# PowerRhythm32.net
KiCad netlist of a schematic drawn in EAGLE
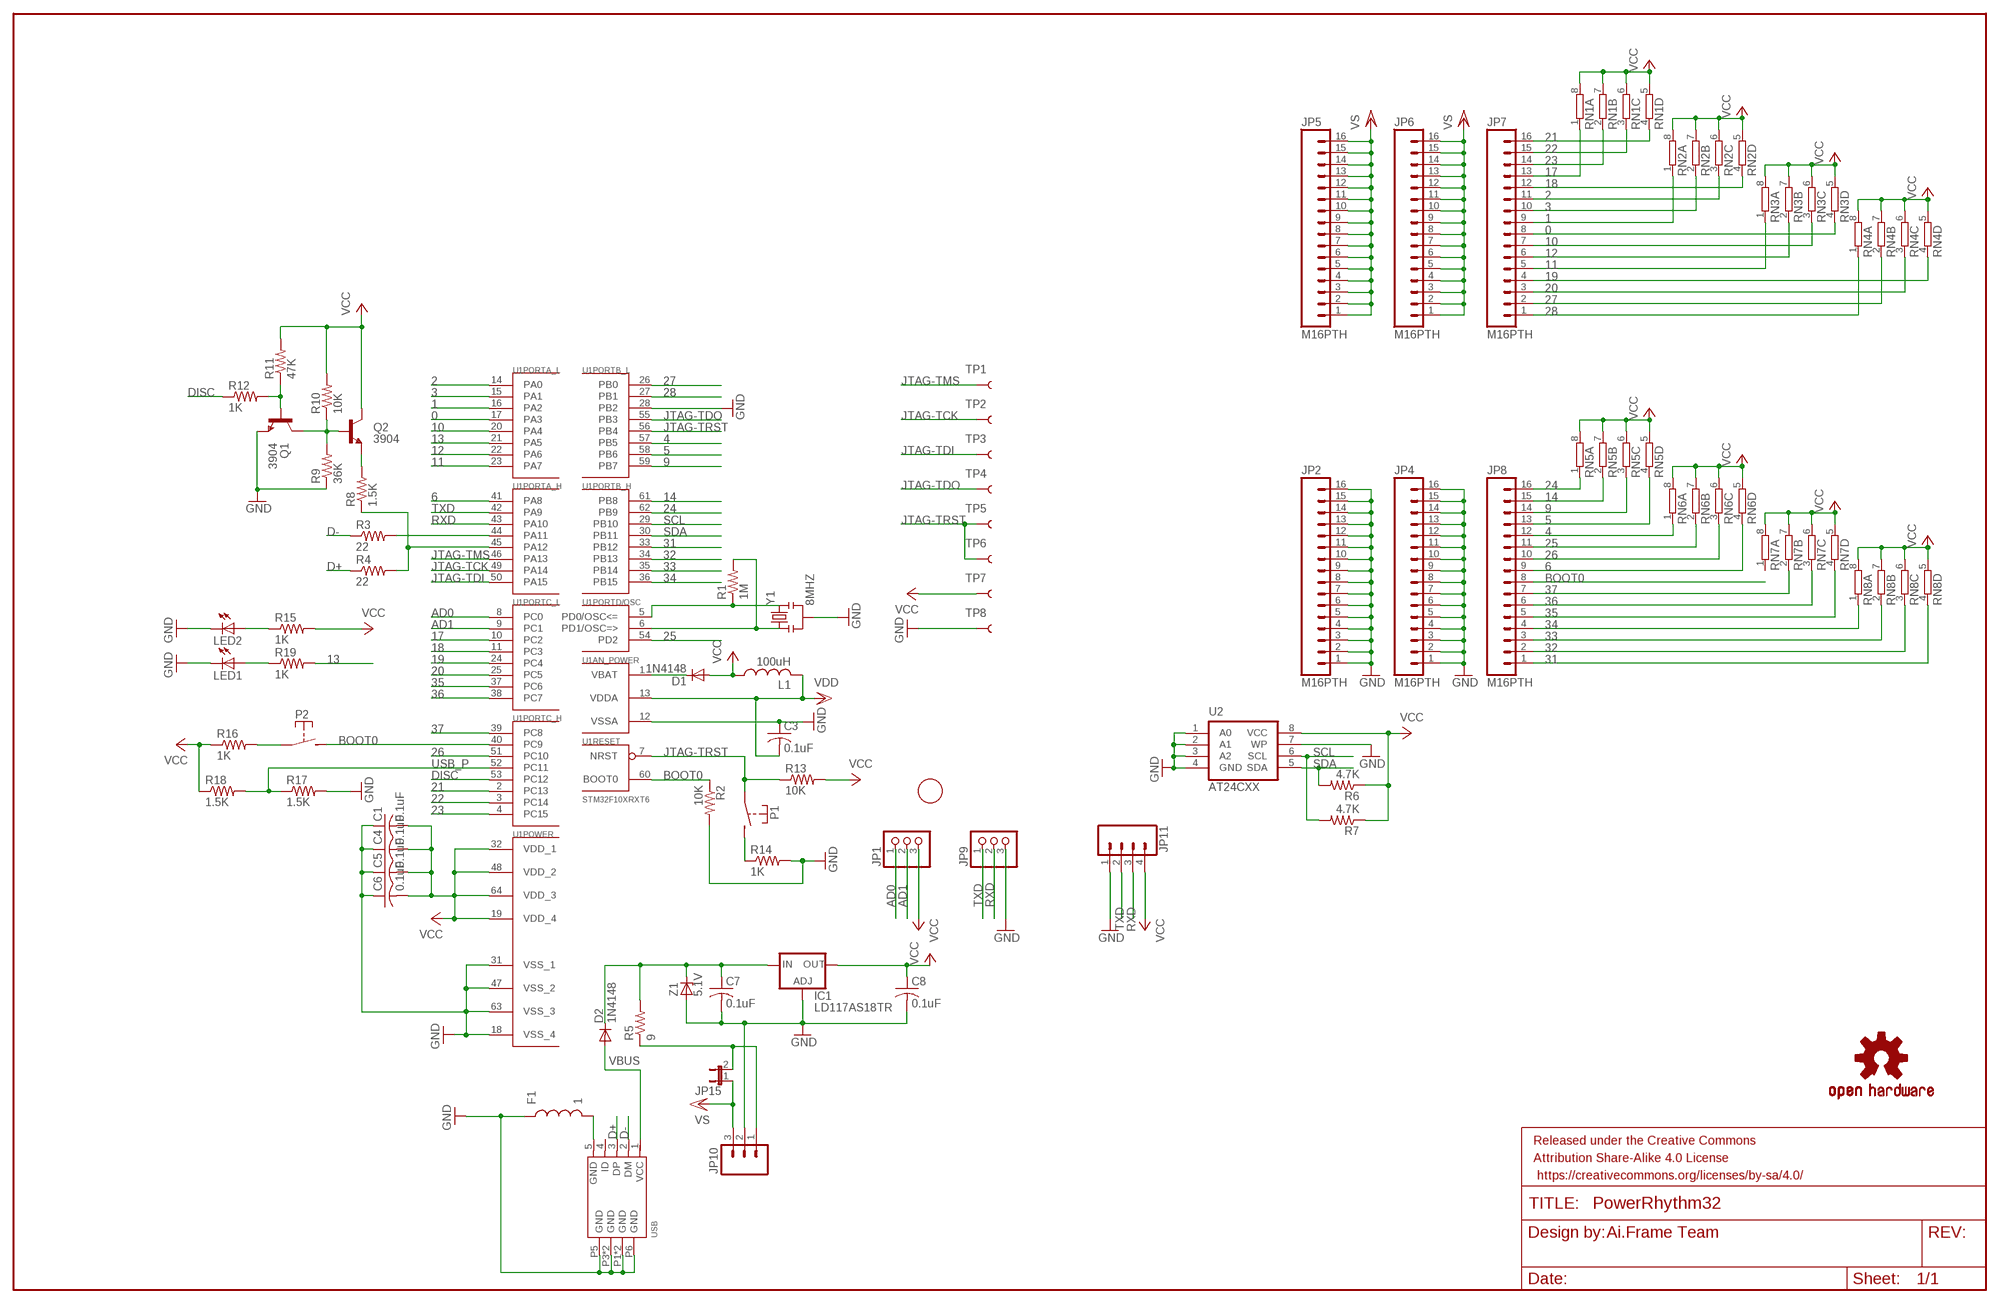
[diagram p0: schematic, sheet 1]

(export (version "E")
  (design (tool "Eeschema 10.0.6"))
  (components
    (comp (ref "C1")
      (value "0.1uF")
      (footprint "eagle-import:C0603K")
      (libsource (lib "eagle-import") (part "C-USC0603K"))
    )
    (comp (ref "C3")
      (value "0.1uF")
      (footprint "eagle-import:C0603K")
      (libsource (lib "eagle-import") (part "C-USC0603K"))
    )
    (comp (ref "C4")
      (value "0.1uF")
      (footprint "eagle-import:C0603K")
      (libsource (lib "eagle-import") (part "C-USC0603K"))
    )
    (comp (ref "C5")
      (value "0.1uF")
      (footprint "eagle-import:C0603K")
      (libsource (lib "eagle-import") (part "C-USC0603K"))
    )
    (comp (ref "C6")
      (value "0.1uF")
      (footprint "eagle-import:C0603K")
      (libsource (lib "eagle-import") (part "C-USC0603K"))
    )
    (comp (ref "C7")
      (value "0.1uF")
      (footprint "eagle-import:C0603K")
      (libsource (lib "eagle-import") (part "C-USC0603K"))
    )
    (comp (ref "C8")
      (value "0.1uF")
      (footprint "eagle-import:C0603K")
      (libsource (lib "eagle-import") (part "C-USC0603K"))
    )
    (comp (ref "D1")
      (value "1N4148")
      (footprint "eagle-import:SOD123")
      (libsource (lib "eagle-import") (part "DIODE-SOD123"))
    )
    (comp (ref "D2")
      (value "1N4148")
      (footprint "eagle-import:SOD123")
      (libsource (lib "eagle-import") (part "DIODE-SOD123"))
    )
    (comp (ref "F1")
      (value "1")
      (footprint "eagle-import:0805")
      (libsource (lib "eagle-import") (part "INDUCTOR0805"))
    )
    (comp (ref "FRAME1")
      (value "FRAME-LEDGER")
      (footprint "eagle-import:CREATIVE_COMMONS")
      (libsource (lib "eagle-import") (part "FRAME-LEDGER"))
    )
    (comp (ref "IC1")
      (value "LD117AS18TR")
      (footprint "eagle-import:SOT223")
      (libsource (lib "eagle-import") (part "LD117A?S18TR"))
    )
    (comp (ref "JP1")
      (value "PINHD-1X3")
      (footprint "eagle-import:1X03")
      (libsource (lib "eagle-import") (part "PINHD-1X3"))
    )
    (comp (ref "JP2")
      (value "M16PTH")
      (footprint "eagle-import:1X16")
      (libsource (lib "eagle-import") (part "M16PTH"))
    )
    (comp (ref "JP4")
      (value "M16PTH")
      (footprint "eagle-import:1X16")
      (libsource (lib "eagle-import") (part "M16PTH"))
    )
    (comp (ref "JP5")
      (value "M16PTH")
      (footprint "eagle-import:1X16")
      (libsource (lib "eagle-import") (part "M16PTH"))
    )
    (comp (ref "JP6")
      (value "M16PTH")
      (footprint "eagle-import:1X16")
      (libsource (lib "eagle-import") (part "M16PTH"))
    )
    (comp (ref "JP7")
      (value "M16PTH")
      (footprint "eagle-import:1X16")
      (libsource (lib "eagle-import") (part "M16PTH"))
    )
    (comp (ref "JP8")
      (value "M16PTH")
      (footprint "eagle-import:1X16")
      (libsource (lib "eagle-import") (part "M16PTH"))
    )
    (comp (ref "JP9")
      (value "PINHD-1X3")
      (footprint "eagle-import:1X03")
      (libsource (lib "eagle-import") (part "PINHD-1X3"))
    )
    (comp (ref "JP10")
      (value "M03SCREW_LOCK")
      (footprint "eagle-import:SCREWTERMINAL-3.5MM-3_LOCK.007S")
      (libsource (lib "eagle-import") (part "M03SCREW_LOCK"))
    )
    (comp (ref "JP11")
      (value "M04PTH")
      (footprint "eagle-import:1X04")
      (libsource (lib "eagle-import") (part "M04PTH"))
    )
    (comp (ref "JP15")
      (value "JUMPER-2PTH")
      (footprint "eagle-import:1X02")
      (libsource (lib "eagle-import") (part "JUMPER-2PTH"))
    )
    (comp (ref "L1")
      (value "100uH")
      (footprint "eagle-import:L2012C")
      (libsource (lib "eagle-import") (part "L-USL2012C"))
    )
    (comp (ref "LED1")
      (value "LEDCHIP-LED0603")
      (footprint "eagle-import:CHIP-LED0603")
      (libsource (lib "eagle-import") (part "LEDCHIP-LED0603"))
    )
    (comp (ref "LED2")
      (value "LEDCHIP-LED0603")
      (footprint "eagle-import:CHIP-LED0603")
      (libsource (lib "eagle-import") (part "LEDCHIP-LED0603"))
    )
    (comp (ref "LOGO1")
      (value "OSHW-LOGOS")
      (footprint "eagle-import:OSHW-LOGO-S")
      (libsource (lib "eagle-import") (part "OSHW-LOGOS"))
    )
    (comp (ref "P1")
      (value "TMAV433BAA")
      (footprint "eagle-import:TMAV433BAA")
      (libsource (lib "eagle-import") (part "TMAV433BAA"))
    )
    (comp (ref "P2")
      (value "TMAV433BAA")
      (footprint "eagle-import:TMAV433BAA")
      (libsource (lib "eagle-import") (part "TMAV433BAA"))
    )
    (comp (ref "Q1")
      (value "3904")
      (footprint "eagle-import:SOT23-3")
      (libsource (lib "eagle-import") (part "TRANSISTOR_NPNMMBT2222A"))
    )
    (comp (ref "Q2")
      (value "3904")
      (footprint "eagle-import:SOT23-3")
      (libsource (lib "eagle-import") (part "TRANSISTOR_NPNMMBT2222A"))
    )
    (comp (ref "R1")
      (value "1M")
      (footprint "eagle-import:R0603")
      (libsource (lib "eagle-import") (part "R-US_R0603"))
    )
    (comp (ref "R2")
      (value "10K")
      (footprint "eagle-import:R0603")
      (libsource (lib "eagle-import") (part "R-US_R0603"))
    )
    (comp (ref "R3")
      (value "22")
      (footprint "eagle-import:R0603")
      (libsource (lib "eagle-import") (part "R-US_R0603"))
    )
    (comp (ref "R4")
      (value "22")
      (footprint "eagle-import:R0603")
      (libsource (lib "eagle-import") (part "R-US_R0603"))
    )
    (comp (ref "R5")
      (value "9")
      (footprint "eagle-import:R1206")
      (libsource (lib "eagle-import") (part "R-US_R1206"))
    )
    (comp (ref "R6")
      (value "4.7K")
      (footprint "eagle-import:R0603")
      (libsource (lib "eagle-import") (part "R-US_R0603"))
    )
    (comp (ref "R7")
      (value "4.7K")
      (footprint "eagle-import:R0603")
      (libsource (lib "eagle-import") (part "R-US_R0603"))
    )
    (comp (ref "R8")
      (value "1.5K")
      (footprint "eagle-import:R0603")
      (libsource (lib "eagle-import") (part "R-US_R0603"))
    )
    (comp (ref "R9")
      (value "36K")
      (footprint "eagle-import:R0603")
      (libsource (lib "eagle-import") (part "R-US_R0603"))
    )
    (comp (ref "R10")
      (value "10K")
      (footprint "eagle-import:R0603")
      (libsource (lib "eagle-import") (part "R-US_R0603"))
    )
    (comp (ref "R11")
      (value "47K")
      (footprint "eagle-import:R0603")
      (libsource (lib "eagle-import") (part "R-US_R0603"))
    )
    (comp (ref "R12")
      (value "1K")
      (footprint "eagle-import:R0603")
      (libsource (lib "eagle-import") (part "R-US_R0603"))
    )
    (comp (ref "R13")
      (value "10K")
      (footprint "eagle-import:R0603")
      (libsource (lib "eagle-import") (part "R-US_R0603"))
    )
    (comp (ref "R14")
      (value "1K")
      (footprint "eagle-import:R0603")
      (libsource (lib "eagle-import") (part "R-US_R0603"))
    )
    (comp (ref "R15")
      (value "1K")
      (footprint "eagle-import:R0603")
      (libsource (lib "eagle-import") (part "R-US_R0603"))
    )
    (comp (ref "R16")
      (value "1K")
      (footprint "eagle-import:R0603")
      (libsource (lib "eagle-import") (part "R-US_R0603"))
    )
    (comp (ref "R17")
      (value "1.5K")
      (footprint "eagle-import:R0603")
      (libsource (lib "eagle-import") (part "R-US_R0603"))
    )
    (comp (ref "R18")
      (value "1.5K")
      (footprint "eagle-import:R0603")
      (libsource (lib "eagle-import") (part "R-US_R0603"))
    )
    (comp (ref "R19")
      (value "1K")
      (footprint "eagle-import:R0603")
      (libsource (lib "eagle-import") (part "R-US_R0603"))
    )
    (comp (ref "RN1")
      (value "4R-N0603-ARC")
      (footprint "eagle-import:0603-ARC")
      (libsource (lib "eagle-import") (part "4R-N0603-ARC"))
    )
    (comp (ref "RN2")
      (value "4R-N0603-ARC")
      (footprint "eagle-import:0603-ARC")
      (libsource (lib "eagle-import") (part "4R-N0603-ARC"))
    )
    (comp (ref "RN3")
      (value "4R-N0603-ARC")
      (footprint "eagle-import:0603-ARC")
      (libsource (lib "eagle-import") (part "4R-N0603-ARC"))
    )
    (comp (ref "RN4")
      (value "4R-N0603-ARC")
      (footprint "eagle-import:0603-ARC")
      (libsource (lib "eagle-import") (part "4R-N0603-ARC"))
    )
    (comp (ref "RN5")
      (value "4R-N0603-ARC")
      (footprint "eagle-import:0603-ARC")
      (libsource (lib "eagle-import") (part "4R-N0603-ARC"))
    )
    (comp (ref "RN6")
      (value "4R-N0603-ARC")
      (footprint "eagle-import:0603-ARC")
      (libsource (lib "eagle-import") (part "4R-N0603-ARC"))
    )
    (comp (ref "RN7")
      (value "4R-N0603-ARC")
      (footprint "eagle-import:0603-ARC")
      (libsource (lib "eagle-import") (part "4R-N0603-ARC"))
    )
    (comp (ref "RN8")
      (value "4R-N0603-ARC")
      (footprint "eagle-import:0603-ARC")
      (libsource (lib "eagle-import") (part "4R-N0603-ARC"))
    )
    (comp (ref "TP1")
      (value "TEST-POINT3X5")
      (footprint "eagle-import:PAD.03X.05")
      (libsource (lib "eagle-import") (part "TEST-POINT3X5"))
    )
    (comp (ref "TP2")
      (value "TEST-POINT3X5")
      (footprint "eagle-import:PAD.03X.05")
      (libsource (lib "eagle-import") (part "TEST-POINT3X5"))
    )
    (comp (ref "TP3")
      (value "TEST-POINT3X5")
      (footprint "eagle-import:PAD.03X.05")
      (libsource (lib "eagle-import") (part "TEST-POINT3X5"))
    )
    (comp (ref "TP4")
      (value "TEST-POINT3X5")
      (footprint "eagle-import:PAD.03X.05")
      (libsource (lib "eagle-import") (part "TEST-POINT3X5"))
    )
    (comp (ref "TP5")
      (value "TEST-POINT3X5")
      (footprint "eagle-import:PAD.03X.05")
      (libsource (lib "eagle-import") (part "TEST-POINT3X5"))
    )
    (comp (ref "TP6")
      (value "TEST-POINT3X5")
      (footprint "eagle-import:PAD.03X.05")
      (libsource (lib "eagle-import") (part "TEST-POINT3X5"))
    )
    (comp (ref "TP7")
      (value "TEST-POINT3X5")
      (footprint "eagle-import:PAD.03X.05")
      (libsource (lib "eagle-import") (part "TEST-POINT3X5"))
    )
    (comp (ref "TP8")
      (value "TEST-POINT3X5")
      (footprint "eagle-import:PAD.03X.05")
      (libsource (lib "eagle-import") (part "TEST-POINT3X5"))
    )
    (comp (ref "U$1")
      (value "FIDUCIAL")
      (footprint "eagle-import:FIDUCIAL_1MM")
      (libsource (lib "eagle-import") (part "FIDUCIAL"))
    )
    (comp (ref "U1")
      (value "STM32F10XRXT6")
      (footprint "eagle-import:TQFP64")
      (libsource (lib "eagle-import") (part "STM32F10XRXT6"))
    )
    (comp (ref "U2")
      (value "AT24CXX")
      (footprint "eagle-import:SO08-8S1")
      (libsource (lib "eagle-import") (part "AT24CXX"))
    )
    (comp (ref "USB")
      (value "MICRO-USB5+4P'5+6P'")
      (footprint "eagle-import:MICRO-USB5+6P-SMD-0.65-AB")
      (libsource (lib "eagle-import") (part "MICRO-USB5+4P'5+6P'"))
    )
    (comp (ref "Y1")
      (value "8MHZ")
      (footprint "eagle-import:RESONATOR-SMD")
      (libsource (lib "eagle-import") (part "RESONATOR8MHZ"))
    )
    (comp (ref "Z1")
      (value "5.1V")
      (footprint "eagle-import:SOD80C")
      (libsource (lib "eagle-import") (part "ZENER-DIODESOD80C"))
    )
  )
  (nets
    (net (code "1") (name "/0") (class "Default")
      (node (ref "JP7") (pin "8") (pinfunction "8_8") (pintype "passive"))
      (node (ref "RN3") (pin "4") (pinfunction "1_4") (pintype "passive"))
      (node (ref "U1") (pin "17") (pinfunction "PA3_17") (pintype "bidirectional"))
    )
    (net (code "2") (name "/1") (class "Default")
      (node (ref "JP7") (pin "9") (pinfunction "9_9") (pintype "passive"))
      (node (ref "RN2") (pin "1") (pinfunction "1_1") (pintype "passive"))
      (node (ref "U1") (pin "16") (pinfunction "PA2_16") (pintype "bidirectional"))
    )
    (net (code "3") (name "/2") (class "Default")
      (node (ref "JP7") (pin "11") (pinfunction "11_11") (pintype "passive"))
      (node (ref "RN2") (pin "3") (pinfunction "1_3") (pintype "passive"))
      (node (ref "U1") (pin "14") (pinfunction "PA0_14") (pintype "bidirectional"))
    )
    (net (code "4") (name "/3") (class "Default")
      (node (ref "JP7") (pin "10") (pinfunction "10_10") (pintype "passive"))
      (node (ref "RN2") (pin "2") (pinfunction "1_2") (pintype "passive"))
      (node (ref "U1") (pin "15") (pinfunction "PA1_15") (pintype "bidirectional"))
    )
    (net (code "5") (name "/4") (class "Default")
      (node (ref "JP8") (pin "12") (pinfunction "12_12") (pintype "passive"))
      (node (ref "RN6") (pin "1") (pinfunction "1_1") (pintype "passive"))
      (node (ref "U1") (pin "57") (pinfunction "PB5_57") (pintype "bidirectional"))
    )
    (net (code "6") (name "/5") (class "Default")
      (node (ref "JP8") (pin "13") (pinfunction "13_13") (pintype "passive"))
      (node (ref "RN5") (pin "4") (pinfunction "1_4") (pintype "passive"))
      (node (ref "U1") (pin "58") (pinfunction "PB6_58") (pintype "bidirectional"))
    )
    (net (code "7") (name "/6") (class "Default")
      (node (ref "JP8") (pin "9") (pinfunction "9_9") (pintype "passive"))
      (node (ref "RN6") (pin "4") (pinfunction "1_4") (pintype "passive"))
      (node (ref "U1") (pin "41") (pinfunction "PA8_41") (pintype "bidirectional"))
    )
    (net (code "8") (name "/9") (class "Default")
      (node (ref "JP8") (pin "14") (pinfunction "14_14") (pintype "passive"))
      (node (ref "RN5") (pin "3") (pinfunction "1_3") (pintype "passive"))
      (node (ref "U1") (pin "59") (pinfunction "PB7_59") (pintype "bidirectional"))
    )
    (net (code "9") (name "/10") (class "Default")
      (node (ref "JP7") (pin "7") (pinfunction "7_7") (pintype "passive"))
      (node (ref "RN3") (pin "3") (pinfunction "1_3") (pintype "passive"))
      (node (ref "U1") (pin "20") (pinfunction "PA4_20") (pintype "bidirectional"))
    )
    (net (code "10") (name "/11") (class "Default")
      (node (ref "JP7") (pin "5") (pinfunction "5_5") (pintype "passive"))
      (node (ref "RN3") (pin "1") (pinfunction "1_1") (pintype "passive"))
      (node (ref "U1") (pin "23") (pinfunction "PA7_23") (pintype "bidirectional"))
    )
    (net (code "11") (name "/12") (class "Default")
      (node (ref "JP7") (pin "6") (pinfunction "6_6") (pintype "passive"))
      (node (ref "RN3") (pin "2") (pinfunction "1_2") (pintype "passive"))
      (node (ref "U1") (pin "22") (pinfunction "PA6_22") (pintype "bidirectional"))
    )
    (net (code "12") (name "/13") (class "Default")
      (node (ref "R19") (pin "2") (pinfunction "2_2") (pintype "passive"))
      (node (ref "U1") (pin "21") (pinfunction "PA5_21") (pintype "bidirectional"))
    )
    (net (code "13") (name "/14") (class "Default")
      (node (ref "JP8") (pin "15") (pinfunction "15_15") (pintype "passive"))
      (node (ref "RN5") (pin "2") (pinfunction "1_2") (pintype "passive"))
      (node (ref "U1") (pin "61") (pinfunction "PB8_61") (pintype "bidirectional"))
    )
    (net (code "14") (name "/17") (class "Default")
      (node (ref "JP7") (pin "13") (pinfunction "13_13") (pintype "passive"))
      (node (ref "RN1") (pin "1") (pinfunction "1_1") (pintype "passive"))
      (node (ref "U1") (pin "10") (pinfunction "PC2_10") (pintype "bidirectional"))
    )
    (net (code "15") (name "/18") (class "Default")
      (node (ref "JP7") (pin "12") (pinfunction "12_12") (pintype "passive"))
      (node (ref "RN2") (pin "4") (pinfunction "1_4") (pintype "passive"))
      (node (ref "U1") (pin "11") (pinfunction "PC3_11") (pintype "bidirectional"))
    )
    (net (code "16") (name "/19") (class "Default")
      (node (ref "JP7") (pin "4") (pinfunction "4_4") (pintype "passive"))
      (node (ref "RN4") (pin "4") (pinfunction "1_4") (pintype "passive"))
      (node (ref "U1") (pin "24") (pinfunction "PC4_24") (pintype "bidirectional"))
    )
    (net (code "17") (name "/20") (class "Default")
      (node (ref "JP7") (pin "3") (pinfunction "3_3") (pintype "passive"))
      (node (ref "RN4") (pin "3") (pinfunction "1_3") (pintype "passive"))
      (node (ref "U1") (pin "25") (pinfunction "PC5_25") (pintype "bidirectional"))
    )
    (net (code "18") (name "/21") (class "Default")
      (node (ref "JP7") (pin "16") (pinfunction "16_16") (pintype "passive"))
      (node (ref "RN1") (pin "4") (pinfunction "1_4") (pintype "passive"))
      (node (ref "U1") (pin "2") (pinfunction "PC13_2") (pintype "bidirectional"))
    )
    (net (code "19") (name "/22") (class "Default")
      (node (ref "JP7") (pin "15") (pinfunction "15_15") (pintype "passive"))
      (node (ref "RN1") (pin "3") (pinfunction "1_3") (pintype "passive"))
      (node (ref "U1") (pin "3") (pinfunction "PC14_3") (pintype "bidirectional"))
    )
    (net (code "20") (name "/23") (class "Default")
      (node (ref "JP7") (pin "14") (pinfunction "14_14") (pintype "passive"))
      (node (ref "RN1") (pin "2") (pinfunction "1_2") (pintype "passive"))
      (node (ref "U1") (pin "4") (pinfunction "PC15_4") (pintype "bidirectional"))
    )
    (net (code "21") (name "/24") (class "Default")
      (node (ref "JP8") (pin "16") (pinfunction "16_16") (pintype "passive"))
      (node (ref "RN5") (pin "1") (pinfunction "1_1") (pintype "passive"))
      (node (ref "U1") (pin "62") (pinfunction "PB9_62") (pintype "bidirectional"))
    )
    (net (code "22") (name "/25") (class "Default")
      (node (ref "JP8") (pin "11") (pinfunction "11_11") (pintype "passive"))
      (node (ref "RN6") (pin "2") (pinfunction "1_2") (pintype "passive"))
      (node (ref "U1") (pin "54") (pinfunction "PD2_54") (pintype "bidirectional"))
    )
    (net (code "23") (name "/26") (class "Default")
      (node (ref "JP8") (pin "10") (pinfunction "10_10") (pintype "passive"))
      (node (ref "RN6") (pin "3") (pinfunction "1_3") (pintype "passive"))
      (node (ref "U1") (pin "51") (pinfunction "PC10_51") (pintype "bidirectional"))
    )
    (net (code "24") (name "/27") (class "Default")
      (node (ref "JP7") (pin "2") (pinfunction "2_2") (pintype "passive"))
      (node (ref "RN4") (pin "2") (pinfunction "1_2") (pintype "passive"))
      (node (ref "U1") (pin "26") (pinfunction "PB0_26") (pintype "bidirectional"))
    )
    (net (code "25") (name "/28") (class "Default")
      (node (ref "JP7") (pin "1") (pinfunction "1_1") (pintype "passive"))
      (node (ref "RN4") (pin "1") (pinfunction "1_1") (pintype "passive"))
      (node (ref "U1") (pin "27") (pinfunction "PB1_27") (pintype "bidirectional"))
    )
    (net (code "26") (name "/31") (class "Default")
      (node (ref "JP8") (pin "1") (pinfunction "1_1") (pintype "passive"))
      (node (ref "RN8") (pin "4") (pinfunction "1_4") (pintype "passive"))
      (node (ref "U1") (pin "33") (pinfunction "PB12_33") (pintype "bidirectional"))
    )
    (net (code "27") (name "/32") (class "Default")
      (node (ref "JP8") (pin "2") (pinfunction "2_2") (pintype "passive"))
      (node (ref "RN8") (pin "3") (pinfunction "1_3") (pintype "passive"))
      (node (ref "U1") (pin "34") (pinfunction "PB13_34") (pintype "bidirectional"))
    )
    (net (code "28") (name "/33") (class "Default")
      (node (ref "JP8") (pin "3") (pinfunction "3_3") (pintype "passive"))
      (node (ref "RN8") (pin "2") (pinfunction "1_2") (pintype "passive"))
      (node (ref "U1") (pin "35") (pinfunction "PB14_35") (pintype "bidirectional"))
    )
    (net (code "29") (name "/34") (class "Default")
      (node (ref "JP8") (pin "4") (pinfunction "4_4") (pintype "passive"))
      (node (ref "RN8") (pin "1") (pinfunction "1_1") (pintype "passive"))
      (node (ref "U1") (pin "36") (pinfunction "PB15_36") (pintype "bidirectional"))
    )
    (net (code "30") (name "/35") (class "Default")
      (node (ref "JP8") (pin "5") (pinfunction "5_5") (pintype "passive"))
      (node (ref "RN7") (pin "4") (pinfunction "1_4") (pintype "passive"))
      (node (ref "U1") (pin "37") (pinfunction "PC6_37") (pintype "bidirectional"))
    )
    (net (code "31") (name "/36") (class "Default")
      (node (ref "JP8") (pin "6") (pinfunction "6_6") (pintype "passive"))
      (node (ref "RN7") (pin "3") (pinfunction "1_3") (pintype "passive"))
      (node (ref "U1") (pin "38") (pinfunction "PC7_38") (pintype "bidirectional"))
    )
    (net (code "32") (name "/37") (class "Default")
      (node (ref "JP8") (pin "7") (pinfunction "7_7") (pintype "passive"))
      (node (ref "RN7") (pin "2") (pinfunction "1_2") (pintype "passive"))
      (node (ref "U1") (pin "39") (pinfunction "PC8_39") (pintype "bidirectional"))
    )
    (net (code "33") (name "/AD0") (class "Default")
      (node (ref "JP1") (pin "1") (pinfunction "1_1") (pintype "passive"))
      (node (ref "U1") (pin "8") (pinfunction "PC0_8") (pintype "bidirectional"))
    )
    (net (code "34") (name "/AD1") (class "Default")
      (node (ref "JP1") (pin "2") (pinfunction "2_2") (pintype "passive"))
      (node (ref "U1") (pin "9") (pinfunction "PC1_9") (pintype "bidirectional"))
    )
    (net (code "35") (name "/BOOT0") (class "Default")
      (node (ref "JP8") (pin "8") (pinfunction "8_8") (pintype "passive"))
      (node (ref "P2") (pin "P$2") (pinfunction "S_P$2") (pintype "passive"))
      (node (ref "R2") (pin "1") (pinfunction "1_1") (pintype "passive"))
      (node (ref "U1") (pin "40") (pinfunction "PC9_40") (pintype "bidirectional"))
      (node (ref "U1") (pin "60") (pinfunction "BOOT0_60") (pintype "input"))
    )
    (net (code "36") (name "/D+") (class "Default")
      (node (ref "R4") (pin "1") (pinfunction "1_1") (pintype "passive"))
      (node (ref "USB") (pin "3") (pinfunction "DP_3") (pintype "bidirectional"))
    )
    (net (code "37") (name "/D-") (class "Default")
      (node (ref "R3") (pin "1") (pinfunction "1_1") (pintype "passive"))
      (node (ref "USB") (pin "2") (pinfunction "DM_2") (pintype "bidirectional"))
    )
    (net (code "38") (name "/DISC") (class "Default")
      (node (ref "R12") (pin "1") (pinfunction "1_1") (pintype "passive"))
      (node (ref "U1") (pin "53") (pinfunction "PC12_53") (pintype "bidirectional"))
    )
    (net (code "39") (name "/JTAG-TCK") (class "Default")
      (node (ref "TP2") (pin "P$1") (pinfunction "1_P$1") (pintype "bidirectional"))
      (node (ref "U1") (pin "49") (pinfunction "PA14_49") (pintype "bidirectional"))
    )
    (net (code "40") (name "/JTAG-TDI") (class "Default")
      (node (ref "TP3") (pin "P$1") (pinfunction "1_P$1") (pintype "bidirectional"))
      (node (ref "U1") (pin "50") (pinfunction "PA15_50") (pintype "bidirectional"))
    )
    (net (code "41") (name "/JTAG-TDO") (class "Default")
      (node (ref "TP4") (pin "P$1") (pinfunction "1_P$1") (pintype "bidirectional"))
      (node (ref "U1") (pin "55") (pinfunction "PB3_55") (pintype "bidirectional"))
    )
    (net (code "42") (name "/JTAG-TMS") (class "Default")
      (node (ref "TP1") (pin "P$1") (pinfunction "1_P$1") (pintype "bidirectional"))
      (node (ref "U1") (pin "46") (pinfunction "PA13_46") (pintype "bidirectional"))
    )
    (net (code "43") (name "/JTAG-TRST") (class "Default")
      (node (ref "P1") (pin "P$1") (pinfunction "P_P$1") (pintype "passive"))
      (node (ref "R13") (pin "1") (pinfunction "1_1") (pintype "passive"))
      (node (ref "TP5") (pin "P$1") (pinfunction "1_P$1") (pintype "bidirectional"))
      (node (ref "TP6") (pin "P$1") (pinfunction "1_P$1") (pintype "bidirectional"))
      (node (ref "U1") (pin "56") (pinfunction "PB4_56") (pintype "bidirectional"))
      (node (ref "U1") (pin "7") (pinfunction "NRST_7") (pintype "input"))
    )
    (net (code "44") (name "/RXD") (class "Default")
      (node (ref "JP11") (pin "3") (pinfunction "3_3") (pintype "passive"))
      (node (ref "JP9") (pin "2") (pinfunction "2_2") (pintype "passive"))
      (node (ref "U1") (pin "43") (pinfunction "PA10_43") (pintype "bidirectional"))
    )
    (net (code "45") (name "/SCL") (class "Default")
      (node (ref "R7") (pin "2") (pinfunction "2_2") (pintype "passive"))
      (node (ref "U1") (pin "29") (pinfunction "PB10_29") (pintype "bidirectional"))
      (node (ref "U2") (pin "6") (pinfunction "SCL_6") (pintype "bidirectional"))
    )
    (net (code "46") (name "/SDA") (class "Default")
      (node (ref "R6") (pin "2") (pinfunction "2_2") (pintype "passive"))
      (node (ref "U1") (pin "30") (pinfunction "PB11_30") (pintype "bidirectional"))
      (node (ref "U2") (pin "5") (pinfunction "SDA_5") (pintype "bidirectional"))
    )
    (net (code "47") (name "/TXD") (class "Default")
      (node (ref "JP11") (pin "2") (pinfunction "2_2") (pintype "passive"))
      (node (ref "JP9") (pin "1") (pinfunction "1_1") (pintype "passive"))
      (node (ref "U1") (pin "42") (pinfunction "PA9_42") (pintype "bidirectional"))
    )
    (net (code "48") (name "/USB_P") (class "Default")
      (node (ref "R17") (pin "1") (pinfunction "1_1") (pintype "passive"))
      (node (ref "R18") (pin "2") (pinfunction "2_2") (pintype "passive"))
      (node (ref "U1") (pin "52") (pinfunction "PC11_52") (pintype "bidirectional"))
    )
    (net (code "49") (name "/VBUS") (class "Default")
      (node (ref "D2") (pin "A") (pinfunction "A_A") (pintype "passive"))
      (node (ref "USB") (pin "1") (pinfunction "VCC_1") (pintype "bidirectional"))
    )
    (net (code "50") (name "GND") (class "Default")
      (node (ref "C1") (pin "1") (pinfunction "1_1") (pintype "passive"))
      (node (ref "C3") (pin "1") (pinfunction "1_1") (pintype "passive"))
      (node (ref "C4") (pin "1") (pinfunction "1_1") (pintype "passive"))
      (node (ref "C5") (pin "1") (pinfunction "1_1") (pintype "passive"))
      (node (ref "C6") (pin "1") (pinfunction "1_1") (pintype "passive"))
      (node (ref "C7") (pin "2") (pinfunction "2_2") (pintype "passive"))
      (node (ref "C8") (pin "2") (pinfunction "2_2") (pintype "passive"))
      (node (ref "F1") (pin "1") (pinfunction "1_1") (pintype "passive"))
      (node (ref "IC1") (pin "1") (pinfunction "ADJ_1") (pintype "input"))
      (node (ref "JP10") (pin "2") (pinfunction "2_2") (pintype "passive"))
      (node (ref "JP11") (pin "1") (pinfunction "1_1") (pintype "passive"))
      (node (ref "JP2") (pin "1") (pinfunction "1_1") (pintype "passive"))
      (node (ref "JP2") (pin "10") (pinfunction "10_10") (pintype "passive"))
      (node (ref "JP2") (pin "11") (pinfunction "11_11") (pintype "passive"))
      (node (ref "JP2") (pin "12") (pinfunction "12_12") (pintype "passive"))
      (node (ref "JP2") (pin "13") (pinfunction "13_13") (pintype "passive"))
      (node (ref "JP2") (pin "14") (pinfunction "14_14") (pintype "passive"))
      (node (ref "JP2") (pin "15") (pinfunction "15_15") (pintype "passive"))
      (node (ref "JP2") (pin "16") (pinfunction "16_16") (pintype "passive"))
      (node (ref "JP2") (pin "2") (pinfunction "2_2") (pintype "passive"))
      (node (ref "JP2") (pin "3") (pinfunction "3_3") (pintype "passive"))
      (node (ref "JP2") (pin "4") (pinfunction "4_4") (pintype "passive"))
      (node (ref "JP2") (pin "5") (pinfunction "5_5") (pintype "passive"))
      (node (ref "JP2") (pin "6") (pinfunction "6_6") (pintype "passive"))
      (node (ref "JP2") (pin "7") (pinfunction "7_7") (pintype "passive"))
      (node (ref "JP2") (pin "8") (pinfunction "8_8") (pintype "passive"))
      (node (ref "JP2") (pin "9") (pinfunction "9_9") (pintype "passive"))
      (node (ref "JP4") (pin "1") (pinfunction "1_1") (pintype "passive"))
      (node (ref "JP4") (pin "10") (pinfunction "10_10") (pintype "passive"))
      (node (ref "JP4") (pin "11") (pinfunction "11_11") (pintype "passive"))
      (node (ref "JP4") (pin "12") (pinfunction "12_12") (pintype "passive"))
      (node (ref "JP4") (pin "13") (pinfunction "13_13") (pintype "passive"))
      (node (ref "JP4") (pin "14") (pinfunction "14_14") (pintype "passive"))
      (node (ref "JP4") (pin "15") (pinfunction "15_15") (pintype "passive"))
      (node (ref "JP4") (pin "16") (pinfunction "16_16") (pintype "passive"))
      (node (ref "JP4") (pin "2") (pinfunction "2_2") (pintype "passive"))
      (node (ref "JP4") (pin "3") (pinfunction "3_3") (pintype "passive"))
      (node (ref "JP4") (pin "4") (pinfunction "4_4") (pintype "passive"))
      (node (ref "JP4") (pin "5") (pinfunction "5_5") (pintype "passive"))
      (node (ref "JP4") (pin "6") (pinfunction "6_6") (pintype "passive"))
      (node (ref "JP4") (pin "7") (pinfunction "7_7") (pintype "passive"))
      (node (ref "JP4") (pin "8") (pinfunction "8_8") (pintype "passive"))
      (node (ref "JP4") (pin "9") (pinfunction "9_9") (pintype "passive"))
      (node (ref "JP9") (pin "3") (pinfunction "3_3") (pintype "passive"))
      (node (ref "LED1") (pin "C") (pinfunction "C_C") (pintype "passive"))
      (node (ref "LED2") (pin "C") (pinfunction "C_C") (pintype "passive"))
      (node (ref "Q1") (pin "2") (pinfunction "E_2") (pintype "passive"))
      (node (ref "R14") (pin "2") (pinfunction "2_2") (pintype "passive"))
      (node (ref "R17") (pin "2") (pinfunction "2_2") (pintype "passive"))
      (node (ref "R2") (pin "2") (pinfunction "2_2") (pintype "passive"))
      (node (ref "R9") (pin "1") (pinfunction "1_1") (pintype "passive"))
      (node (ref "TP8") (pin "P$1") (pinfunction "1_P$1") (pintype "bidirectional"))
      (node (ref "U1") (pin "12") (pinfunction "VSSA_12") (pintype "power_in"))
      (node (ref "U1") (pin "18") (pinfunction "VSS_4_18") (pintype "power_in"))
      (node (ref "U1") (pin "28") (pinfunction "PB2_28") (pintype "bidirectional"))
      (node (ref "U1") (pin "31") (pinfunction "VSS_1_31") (pintype "power_in"))
      (node (ref "U1") (pin "47") (pinfunction "VSS_2_47") (pintype "power_in"))
      (node (ref "U1") (pin "63") (pinfunction "VSS_3_63") (pintype "power_in"))
      (node (ref "U2") (pin "1") (pinfunction "A0_1") (pintype "input"))
      (node (ref "U2") (pin "2") (pinfunction "A1_2") (pintype "input"))
      (node (ref "U2") (pin "3") (pinfunction "A2_3") (pintype "input"))
      (node (ref "U2") (pin "4") (pinfunction "GND_4") (pintype "power_in"))
      (node (ref "U2") (pin "7") (pinfunction "WP_7") (pintype "bidirectional"))
      (node (ref "USB") (pin "P1") (pinfunction "GND_P1") (pintype "bidirectional"))
      (node (ref "USB") (pin "P2") (pinfunction "GND_P2") (pintype "bidirectional"))
      (node (ref "USB") (pin "P3") (pinfunction "GND_P3") (pintype "bidirectional"))
      (node (ref "USB") (pin "P4") (pinfunction "GND_P4") (pintype "bidirectional"))
      (node (ref "USB") (pin "P5") (pinfunction "GND_P5") (pintype "bidirectional"))
      (node (ref "USB") (pin "P6") (pinfunction "GND_P6") (pintype "bidirectional"))
      (node (ref "Y1") (pin "2") (pinfunction "2_2") (pintype "passive"))
      (node (ref "Z1") (pin "A") (pinfunction "A_A") (pintype "passive"))
    )
    (net (code "51") (name "Net-(F1-Pad2)") (class "Default")
      (node (ref "F1") (pin "2") (pinfunction "2_2") (pintype "passive"))
      (node (ref "USB") (pin "5") (pinfunction "GND_5") (pintype "bidirectional"))
    )
    (net (code "52") (name "Net-(IC1-IN)") (class "Default")
      (node (ref "C7") (pin "1") (pinfunction "1_1") (pintype "passive"))
      (node (ref "D2") (pin "C") (pinfunction "C_C") (pintype "passive"))
      (node (ref "IC1") (pin "3") (pinfunction "IN_3") (pintype "input"))
      (node (ref "R5") (pin "2") (pinfunction "2_2") (pintype "passive"))
      (node (ref "Z1") (pin "C") (pinfunction "C_C") (pintype "passive"))
    )
    (net (code "53") (name "Net-(JP10-Pad1)") (class "Default")
      (node (ref "JP10") (pin "1") (pinfunction "1_1") (pintype "passive"))
      (node (ref "JP15") (pin "2") (pinfunction "2_2") (pintype "passive"))
      (node (ref "R5") (pin "1") (pinfunction "1_1") (pintype "passive"))
    )
    (net (code "54") (name "Net-(LED1-PadA)") (class "Default")
      (node (ref "LED1") (pin "A") (pinfunction "A_A") (pintype "passive"))
      (node (ref "R19") (pin "1") (pinfunction "1_1") (pintype "passive"))
    )
    (net (code "55") (name "Net-(LED2-PadA)") (class "Default")
      (node (ref "LED2") (pin "A") (pinfunction "A_A") (pintype "passive"))
      (node (ref "R15") (pin "1") (pinfunction "1_1") (pintype "passive"))
    )
    (net (code "56") (name "Net-(P1-S)") (class "Default")
      (node (ref "P1") (pin "P$2") (pinfunction "S_P$2") (pintype "passive"))
      (node (ref "R14") (pin "1") (pinfunction "1_1") (pintype "passive"))
    )
    (net (code "57") (name "Net-(P2-P)") (class "Default")
      (node (ref "P2") (pin "P$1") (pinfunction "P_P$1") (pintype "passive"))
      (node (ref "R16") (pin "2") (pinfunction "2_2") (pintype "passive"))
    )
    (net (code "58") (name "Net-(Q1-B)") (class "Default")
      (node (ref "Q1") (pin "1") (pinfunction "B_1") (pintype "passive"))
      (node (ref "R11") (pin "1") (pinfunction "1_1") (pintype "passive"))
      (node (ref "R12") (pin "2") (pinfunction "2_2") (pintype "passive"))
    )
    (net (code "59") (name "Net-(Q1-C)") (class "Default")
      (node (ref "Q1") (pin "3") (pinfunction "C_3") (pintype "passive"))
      (node (ref "Q2") (pin "1") (pinfunction "B_1") (pintype "passive"))
      (node (ref "R10") (pin "1") (pinfunction "1_1") (pintype "passive"))
      (node (ref "R9") (pin "2") (pinfunction "2_2") (pintype "passive"))
    )
    (net (code "60") (name "Net-(Q2-E)") (class "Default")
      (node (ref "Q2") (pin "2") (pinfunction "E_2") (pintype "passive"))
      (node (ref "R8") (pin "2") (pinfunction "2_2") (pintype "passive"))
    )
    (net (code "61") (name "Net-(U1A-VBAT)") (class "Default")
      (node (ref "D1") (pin "C") (pinfunction "C_C") (pintype "passive"))
      (node (ref "U1") (pin "1") (pinfunction "VBAT_1") (pintype "power_in"))
    )
    (net (code "62") (name "Net-(U1B-PA11)") (class "Default")
      (node (ref "R3") (pin "2") (pinfunction "2_2") (pintype "passive"))
      (node (ref "U1") (pin "44") (pinfunction "PA11_44") (pintype "bidirectional"))
    )
    (net (code "63") (name "Net-(U1B-PA12)") (class "Default")
      (node (ref "R4") (pin "2") (pinfunction "2_2") (pintype "passive"))
      (node (ref "R8") (pin "1") (pinfunction "1_1") (pintype "passive"))
      (node (ref "U1") (pin "45") (pinfunction "PA12_45") (pintype "bidirectional"))
    )
    (net (code "64") (name "Net-(U1H-PD0{slash}OSC<=)") (class "Default")
      (node (ref "R1") (pin "1") (pinfunction "1_1") (pintype "passive"))
      (node (ref "U1") (pin "5") (pinfunction "PD0/OSC<=_5") (pintype "bidirectional"))
      (node (ref "Y1") (pin "3") (pinfunction "3_3") (pintype "passive"))
    )
    (net (code "65") (name "Net-(U1H-PD1{slash}OSC=>)") (class "Default")
      (node (ref "R1") (pin "2") (pinfunction "2_2") (pintype "passive"))
      (node (ref "U1") (pin "6") (pinfunction "PD1/OSC=>_6") (pintype "bidirectional"))
      (node (ref "Y1") (pin "1") (pinfunction "1_1") (pintype "passive"))
    )
    (net (code "66") (name "VCC") (class "Default")
      (node (ref "C1") (pin "2") (pinfunction "2_2") (pintype "passive"))
      (node (ref "C4") (pin "2") (pinfunction "2_2") (pintype "passive"))
      (node (ref "C5") (pin "2") (pinfunction "2_2") (pintype "passive"))
      (node (ref "C6") (pin "2") (pinfunction "2_2") (pintype "passive"))
      (node (ref "C8") (pin "1") (pinfunction "1_1") (pintype "passive"))
      (node (ref "D1") (pin "A") (pinfunction "A_A") (pintype "passive"))
      (node (ref "IC1") (pin "4") (pinfunction "OUT_4") (pintype "passive"))
      (node (ref "JP1") (pin "3") (pinfunction "3_3") (pintype "passive"))
      (node (ref "JP11") (pin "4") (pinfunction "4_4") (pintype "passive"))
      (node (ref "L1") (pin "1") (pinfunction "1_1") (pintype "passive"))
      (node (ref "Q2") (pin "3") (pinfunction "C_3") (pintype "passive"))
      (node (ref "R10") (pin "2") (pinfunction "2_2") (pintype "passive"))
      (node (ref "R11") (pin "2") (pinfunction "2_2") (pintype "passive"))
      (node (ref "R13") (pin "2") (pinfunction "2_2") (pintype "passive"))
      (node (ref "R15") (pin "2") (pinfunction "2_2") (pintype "passive"))
      (node (ref "R16") (pin "1") (pinfunction "1_1") (pintype "passive"))
      (node (ref "R18") (pin "1") (pinfunction "1_1") (pintype "passive"))
      (node (ref "R6") (pin "1") (pinfunction "1_1") (pintype "passive"))
      (node (ref "R7") (pin "1") (pinfunction "1_1") (pintype "passive"))
      (node (ref "RN1") (pin "5") (pinfunction "2_5") (pintype "passive"))
      (node (ref "RN1") (pin "6") (pinfunction "2_6") (pintype "passive"))
      (node (ref "RN1") (pin "7") (pinfunction "2_7") (pintype "passive"))
      (node (ref "RN1") (pin "8") (pinfunction "2_8") (pintype "passive"))
      (node (ref "RN2") (pin "5") (pinfunction "2_5") (pintype "passive"))
      (node (ref "RN2") (pin "6") (pinfunction "2_6") (pintype "passive"))
      (node (ref "RN2") (pin "7") (pinfunction "2_7") (pintype "passive"))
      (node (ref "RN2") (pin "8") (pinfunction "2_8") (pintype "passive"))
      (node (ref "RN3") (pin "5") (pinfunction "2_5") (pintype "passive"))
      (node (ref "RN3") (pin "6") (pinfunction "2_6") (pintype "passive"))
      (node (ref "RN3") (pin "7") (pinfunction "2_7") (pintype "passive"))
      (node (ref "RN3") (pin "8") (pinfunction "2_8") (pintype "passive"))
      (node (ref "RN4") (pin "5") (pinfunction "2_5") (pintype "passive"))
      (node (ref "RN4") (pin "6") (pinfunction "2_6") (pintype "passive"))
      (node (ref "RN4") (pin "7") (pinfunction "2_7") (pintype "passive"))
      (node (ref "RN4") (pin "8") (pinfunction "2_8") (pintype "passive"))
      (node (ref "RN5") (pin "5") (pinfunction "2_5") (pintype "passive"))
      (node (ref "RN5") (pin "6") (pinfunction "2_6") (pintype "passive"))
      (node (ref "RN5") (pin "7") (pinfunction "2_7") (pintype "passive"))
      (node (ref "RN5") (pin "8") (pinfunction "2_8") (pintype "passive"))
      (node (ref "RN6") (pin "5") (pinfunction "2_5") (pintype "passive"))
      (node (ref "RN6") (pin "6") (pinfunction "2_6") (pintype "passive"))
      (node (ref "RN6") (pin "7") (pinfunction "2_7") (pintype "passive"))
      (node (ref "RN6") (pin "8") (pinfunction "2_8") (pintype "passive"))
      (node (ref "RN7") (pin "5") (pinfunction "2_5") (pintype "passive"))
      (node (ref "RN7") (pin "6") (pinfunction "2_6") (pintype "passive"))
      (node (ref "RN7") (pin "7") (pinfunction "2_7") (pintype "passive"))
      (node (ref "RN7") (pin "8") (pinfunction "2_8") (pintype "passive"))
      (node (ref "RN8") (pin "5") (pinfunction "2_5") (pintype "passive"))
      (node (ref "RN8") (pin "6") (pinfunction "2_6") (pintype "passive"))
      (node (ref "RN8") (pin "7") (pinfunction "2_7") (pintype "passive"))
      (node (ref "RN8") (pin "8") (pinfunction "2_8") (pintype "passive"))
      (node (ref "TP7") (pin "P$1") (pinfunction "1_P$1") (pintype "bidirectional"))
      (node (ref "U1") (pin "19") (pinfunction "VDD_4_19") (pintype "power_in"))
      (node (ref "U1") (pin "32") (pinfunction "VDD_1_32") (pintype "power_in"))
      (node (ref "U1") (pin "48") (pinfunction "VDD_2_48") (pintype "power_in"))
      (node (ref "U1") (pin "64") (pinfunction "VDD_3_64") (pintype "power_in"))
      (node (ref "U2") (pin "8") (pinfunction "VCC_8") (pintype "power_in"))
    )
    (net (code "67") (name "VDD") (class "Default")
      (node (ref "C3") (pin "2") (pinfunction "2_2") (pintype "passive"))
      (node (ref "L1") (pin "2") (pinfunction "2_2") (pintype "passive"))
      (node (ref "U1") (pin "13") (pinfunction "VDDA_13") (pintype "power_in"))
    )
    (net (code "68") (name "VS") (class "Default")
      (node (ref "JP10") (pin "3") (pinfunction "3_3") (pintype "passive"))
      (node (ref "JP15") (pin "1") (pinfunction "1_1") (pintype "passive"))
      (node (ref "JP5") (pin "1") (pinfunction "1_1") (pintype "passive"))
      (node (ref "JP5") (pin "10") (pinfunction "10_10") (pintype "passive"))
      (node (ref "JP5") (pin "11") (pinfunction "11_11") (pintype "passive"))
      (node (ref "JP5") (pin "12") (pinfunction "12_12") (pintype "passive"))
      (node (ref "JP5") (pin "13") (pinfunction "13_13") (pintype "passive"))
      (node (ref "JP5") (pin "14") (pinfunction "14_14") (pintype "passive"))
      (node (ref "JP5") (pin "15") (pinfunction "15_15") (pintype "passive"))
      (node (ref "JP5") (pin "16") (pinfunction "16_16") (pintype "passive"))
      (node (ref "JP5") (pin "2") (pinfunction "2_2") (pintype "passive"))
      (node (ref "JP5") (pin "3") (pinfunction "3_3") (pintype "passive"))
      (node (ref "JP5") (pin "4") (pinfunction "4_4") (pintype "passive"))
      (node (ref "JP5") (pin "5") (pinfunction "5_5") (pintype "passive"))
      (node (ref "JP5") (pin "6") (pinfunction "6_6") (pintype "passive"))
      (node (ref "JP5") (pin "7") (pinfunction "7_7") (pintype "passive"))
      (node (ref "JP5") (pin "8") (pinfunction "8_8") (pintype "passive"))
      (node (ref "JP5") (pin "9") (pinfunction "9_9") (pintype "passive"))
      (node (ref "JP6") (pin "1") (pinfunction "1_1") (pintype "passive"))
      (node (ref "JP6") (pin "10") (pinfunction "10_10") (pintype "passive"))
      (node (ref "JP6") (pin "11") (pinfunction "11_11") (pintype "passive"))
      (node (ref "JP6") (pin "12") (pinfunction "12_12") (pintype "passive"))
      (node (ref "JP6") (pin "13") (pinfunction "13_13") (pintype "passive"))
      (node (ref "JP6") (pin "14") (pinfunction "14_14") (pintype "passive"))
      (node (ref "JP6") (pin "15") (pinfunction "15_15") (pintype "passive"))
      (node (ref "JP6") (pin "16") (pinfunction "16_16") (pintype "passive"))
      (node (ref "JP6") (pin "2") (pinfunction "2_2") (pintype "passive"))
      (node (ref "JP6") (pin "3") (pinfunction "3_3") (pintype "passive"))
      (node (ref "JP6") (pin "4") (pinfunction "4_4") (pintype "passive"))
      (node (ref "JP6") (pin "5") (pinfunction "5_5") (pintype "passive"))
      (node (ref "JP6") (pin "6") (pinfunction "6_6") (pintype "passive"))
      (node (ref "JP6") (pin "7") (pinfunction "7_7") (pintype "passive"))
      (node (ref "JP6") (pin "8") (pinfunction "8_8") (pintype "passive"))
      (node (ref "JP6") (pin "9") (pinfunction "9_9") (pintype "passive"))
    )
    (net (code "69") (name "unconnected-(RN7-Pad1)") (class "Default")
      (node (ref "RN7") (pin "1") (pinfunction "1_1") (pintype "passive"))
    )
    (net (code "70") (name "unconnected-(USB-ID-Pad4)") (class "Default")
      (node (ref "USB") (pin "4") (pinfunction "ID_4") (pintype "bidirectional"))
    )
  )
)
